# LCL_Atari_Punk_V2.net
KiCad netlist of a schematic drawn in Altium Designer
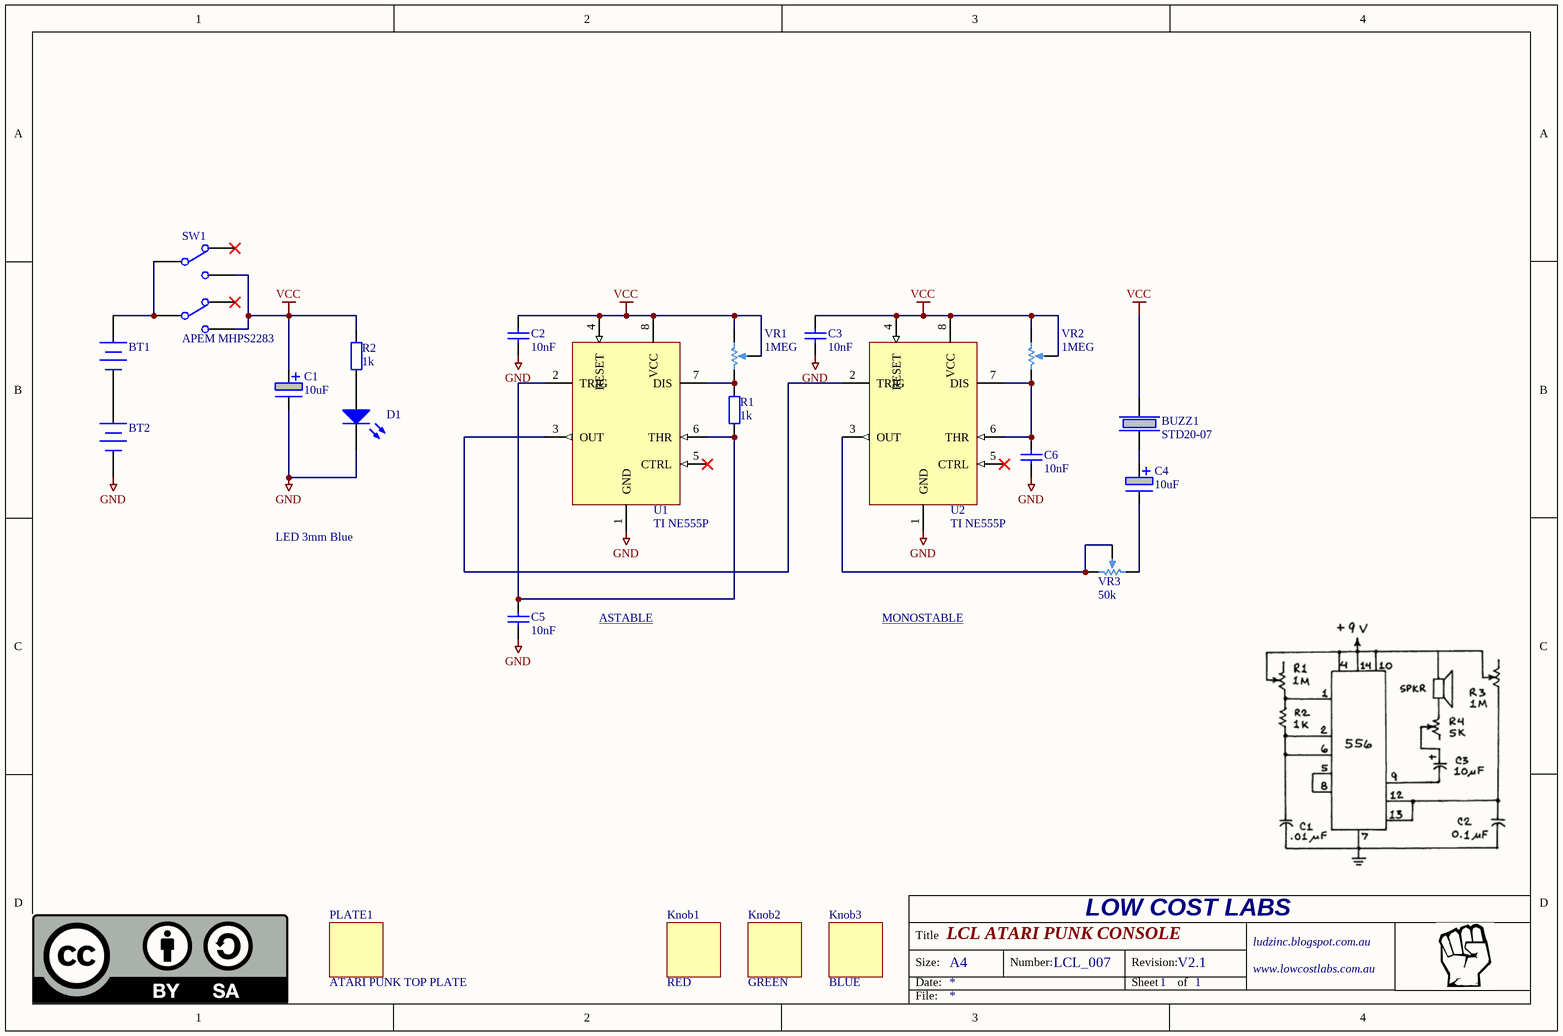
[diagram p0: LCL Atari Punk V2.SchDoc]

(export (version "E")
  (design (tool "Eeschema 10.0.6"))
  (components
    (comp (ref "BT1")
      (value "CR2032 Battery Holder")
      (footprint "PCB-dvcba8mzfnv4aqscf1uc-1")
      (description "CR2032 Battery Holder, Through Hole, Horizontal Mount")
      (libsource (lib "FavoritesLibrary") (part "SYM-19301741-1"))
    )
    (comp (ref "BT2")
      (value "CR2032 Battery Holder")
      (footprint "PCB-dvcba8mzfnv4aqscf1uc-1")
      (description "CR2032 Battery Holder, Through Hole, Horizontal Mount")
      (libsource (lib "FavoritesLibrary") (part "SYM-19301741-1"))
    )
    (comp (ref "BUZZ1")
      (value "STD20-07")
      (footprint "PCB-fy5tm47je2z5a6wt53fs-1")
      (description "BUZZER STD20-07 (EFM2060) PIEZO PASSIVE BUZZER")
      (libsource (lib "FavoritesLibrary") (part "SYM-6939a03a5900b6fe-1"))
    )
    (comp (ref "C1")
      (value "10uF")
      (footprint "PCB-ekxurobr9mz5kbw5d2ks-1")
      (description "5mm Through Hole Electrolytic 2mm Pitch, 5mm height")
      (libsource (lib "FavoritesLibrary") (part "SYM-su2zmkw1kc3z49ns9isd-1"))
    )
    (comp (ref "C2")
      (value "10nF")
      (footprint "PCB-5q3b1ntq00bqadu474q8-1")
      (description "Capacitor, Ceramic, 10000pF, 50VDC, 20-% Tol, 20+% Tol, X7R-TC Code, -15, 15%-TC")
      (fields (field (name "MANUFACTURER PART NUMBER") "C315C103M5R5TA"))
      (libsource (lib "FavoritesLibrary") (part "SYM-f9eb30fd1b76262c-1"))
    )
    (comp (ref "C3")
      (value "10nF")
      (footprint "PCB-5q3b1ntq00bqadu474q8-1")
      (description "Capacitor, Ceramic, 10000pF, 50VDC, 20-% Tol, 20+% Tol, X7R-TC Code, -15, 15%-TC")
      (fields (field (name "MANUFACTURER PART NUMBER") "C315C103M5R5TA"))
      (libsource (lib "FavoritesLibrary") (part "SYM-f9eb30fd1b76262c-1"))
    )
    (comp (ref "C4")
      (value "10uF")
      (footprint "PCB-ekxurobr9mz5kbw5d2ks-1")
      (description "5mm Through Hole Electrolytic 2mm Pitch, 5mm height")
      (libsource (lib "FavoritesLibrary") (part "SYM-su2zmkw1kc3z49ns9isd-1"))
    )
    (comp (ref "C5")
      (value "10nF")
      (footprint "PCB-5q3b1ntq00bqadu474q8-1")
      (description "Capacitor, Ceramic, 10000pF, 50VDC, 20-% Tol, 20+% Tol, X7R-TC Code, -15, 15%-TC")
      (fields (field (name "MANUFACTURER PART NUMBER") "C315C103M5R5TA"))
      (libsource (lib "FavoritesLibrary") (part "SYM-f9eb30fd1b76262c-1"))
    )
    (comp (ref "C6")
      (value "10nF")
      (footprint "PCB-5q3b1ntq00bqadu474q8-1")
      (description "Capacitor, Ceramic, 10000pF, 50VDC, 20-% Tol, 20+% Tol, X7R-TC Code, -15, 15%-TC")
      (fields (field (name "MANUFACTURER PART NUMBER") "C315C103M5R5TA"))
      (libsource (lib "FavoritesLibrary") (part "SYM-f9eb30fd1b76262c-1"))
    )
    (comp (ref "D1")
      (value "LED 3mm Blue")
      (footprint "PCB-6aozigmjsxd1tpg9bi5a-1")
      (description "3mm Blue Through Hole LED")
      (libsource (lib "FavoritesLibrary") (part "SYM-tzej1yqmv3j3170hmi0g-1"))
    )
    (comp (ref "Knob1")
      (value "RED")
      (footprint "PCB-uiy5h88ywsirsj7o87r0-1")
      (description "Pot Knob")
      (libsource (lib "FavoritesLibrary") (part "SYM-8ktywbehqx0aixue8nez-1"))
    )
    (comp (ref "Knob2")
      (value "GREEN")
      (footprint "PCB-uiy5h88ywsirsj7o87r0-1")
      (description "Pot Knob")
      (libsource (lib "FavoritesLibrary") (part "SYM-8ktywbehqx0aixue8nez-1"))
    )
    (comp (ref "Knob3")
      (value "BLUE")
      (footprint "PCB-uiy5h88ywsirsj7o87r0-1")
      (description "Pot Knob")
      (libsource (lib "FavoritesLibrary") (part "SYM-8ktywbehqx0aixue8nez-1"))
    )
    (comp (ref "PLATE1")
      (value "ATARI PUNK TOP PLATE")
      (footprint "PCB-r61ct1i2zrjc296u1a17-1")
      (description "ATARI PUNK TOP PLATE ASSEMBLY WITH 10mm STANDOFFS AND SCREWS")
      (libsource (lib "CommunityVault") (part "SYM-m1ejk5tgbv5wzvnlhkp4-1"))
    )
    (comp (ref "R1")
      (value "1k")
      (footprint "PCB-ixiz65tg090k47x3fmi7-1")
      (description "RESISITOR THROUGH HOLE 1/4W")
      (libsource (lib "FavoritesLibrary") (part "SYM-iaxfckaaxq3jb0c9euu5-1"))
    )
    (comp (ref "R2")
      (value "1k")
      (footprint "PCB-ixiz65tg090k47x3fmi7-1")
      (description "RESISITOR THROUGH HOLE 1/4W")
      (libsource (lib "FavoritesLibrary") (part "SYM-iaxfckaaxq3jb0c9euu5-1"))
    )
    (comp (ref "SW1")
      (value "APEM MHPS2283")
      (footprint "PCB-3xh7x2auc3uid3bxc76z-1")
      (description "Switch Key DPDT 0.1A 30VDC 1.76N PC Pins Thru-Hole")
      (libsource (lib "CommunityVault") (part "SYM-64d5adcf469dbb12-1"))
    )
    (comp (ref "U1")
      (value "TI NE555P")
      (footprint "DIP8-2.54-10.9X6.6MM")
      (description "Peripheral circuit; astable/monostable, timer; 10 V; 500kHz; DIP8")
      (fields (field (name "MANUFACTURER PART NUMBER") "NE555P"))
      (libsource (lib "FavoritesLibrary") (part "TI-NE555-P8"))
    )
    (comp (ref "U2")
      (value "TI NE555P")
      (footprint "DIP8-2.54-10.9X6.6MM")
      (description "Peripheral circuit; astable/monostable, timer; 10 V; 500kHz; DIP8")
      (fields (field (name "MANUFACTURER PART NUMBER") "NE555P"))
      (libsource (lib "FavoritesLibrary") (part "TI-NE555-P8"))
    )
    (comp (ref "VR1")
      (value "1MEG")
      (footprint "PCB-wc6scyizddradfuod10o-1")
      (description "P090 Series 9 mm Top Adjustment 10 kOhm ±20 % Shaft Rotary Potentiometer")
      (fields (field (name "MANUFACTURER PART NUMBER") "P090S-14T20BR10K") (field (name "Comment") "Res1"))
      (libsource (lib "CommunityVault") (part "CMP-9d2d547574b442ea-5"))
    )
    (comp (ref "VR2")
      (value "1MEG")
      (footprint "PCB-wc6scyizddradfuod10o-1")
      (description "P090 Series 9 mm Top Adjustment 10 kOhm ±20 % Shaft Rotary Potentiometer")
      (fields (field (name "MANUFACTURER PART NUMBER") "P090S-14T20BR10K") (field (name "Comment") "Res1"))
      (libsource (lib "CommunityVault") (part "CMP-9d2d547574b442ea-5"))
    )
    (comp (ref "VR3")
      (value "50k")
      (footprint "PCB-wc6scyizddradfuod10o-1")
      (description "P090 Series 9 mm Top Adjustment 10 kOhm ±20 % Shaft Rotary Potentiometer")
      (fields (field (name "MANUFACTURER PART NUMBER") "P090S-14T20BR10K") (field (name "Comment") "Res1"))
      (libsource (lib "CommunityVault") (part "CMP-9d2d547574b442ea-5"))
    )
  )
  (nets
    (net (code "1") (name "GND") (class "Default")
      (node (ref "BT2") (pin "2") (pinfunction "-_2") (pintype "passive"))
      (node (ref "C1") (pin "2") (pinfunction "2_2") (pintype "passive"))
      (node (ref "C2") (pin "1") (pinfunction "1_1") (pintype "passive"))
      (node (ref "C3") (pin "1") (pinfunction "1_1") (pintype "passive"))
      (node (ref "C5") (pin "1") (pinfunction "1_1") (pintype "passive"))
      (node (ref "C6") (pin "1") (pinfunction "1_1") (pintype "passive"))
      (node (ref "D1") (pin "2") (pinfunction "K_2") (pintype "passive"))
      (node (ref "U1") (pin "1") (pinfunction "GND_1") (pintype "power_in"))
      (node (ref "U2") (pin "1") (pinfunction "GND_1") (pintype "power_in"))
    )
    (net (code "2") (name "Net-(BT1-+)") (class "Default")
      (node (ref "BT1") (pin "1") (pinfunction "+_1") (pintype "passive"))
      (node (ref "SW1") (pin "1") (pinfunction "NO1_1") (pintype "passive"))
      (node (ref "SW1") (pin "6") (pinfunction "NO2_6") (pintype "passive"))
    )
    (net (code "3") (name "Net-(BT1--)") (class "Default")
      (node (ref "BT1") (pin "2") (pinfunction "-_2") (pintype "passive"))
      (node (ref "BT2") (pin "1") (pinfunction "+_1") (pintype "passive"))
    )
    (net (code "4") (name "Net-(BUZZ1-Pad2)") (class "Default")
      (node (ref "BUZZ1") (pin "2") (pinfunction "2_2") (pintype "passive"))
      (node (ref "C4") (pin "1") (pinfunction "1_1") (pintype "passive"))
    )
    (net (code "5") (name "Net-(D1-A)") (class "Default")
      (node (ref "D1") (pin "1") (pinfunction "A_1") (pintype "passive"))
      (node (ref "R2") (pin "1") (pinfunction "1_1") (pintype "passive"))
    )
    (net (code "6") (name "Net-(U1-DIS)") (class "Default")
      (node (ref "R1") (pin "2") (pinfunction "2_2") (pintype "passive"))
      (node (ref "U1") (pin "7") (pinfunction "DIS_7") (pintype "open_collector"))
      (node (ref "VR1") (pin "3") (pinfunction "BOT_3") (pintype "passive"))
    )
    (net (code "7") (name "Net-(U1-OUT)") (class "Default")
      (node (ref "U1") (pin "3") (pinfunction "OUT_3") (pintype "output"))
      (node (ref "U2") (pin "2") (pinfunction "TRIG_2") (pintype "passive"))
    )
    (net (code "8") (name "Net-(U1-THR)") (class "Default")
      (node (ref "C5") (pin "2") (pinfunction "2_2") (pintype "passive"))
      (node (ref "R1") (pin "1") (pinfunction "1_1") (pintype "passive"))
      (node (ref "U1") (pin "2") (pinfunction "TRIG_2") (pintype "passive"))
      (node (ref "U1") (pin "6") (pinfunction "THR_6") (pintype "input"))
    )
    (net (code "9") (name "Net-(U2-DIS)") (class "Default")
      (node (ref "C6") (pin "2") (pinfunction "2_2") (pintype "passive"))
      (node (ref "U2") (pin "6") (pinfunction "THR_6") (pintype "input"))
      (node (ref "U2") (pin "7") (pinfunction "DIS_7") (pintype "open_collector"))
      (node (ref "VR2") (pin "3") (pinfunction "BOT_3") (pintype "passive"))
    )
    (net (code "10") (name "Net-(U2-OUT)") (class "Default")
      (node (ref "U2") (pin "3") (pinfunction "OUT_3") (pintype "output"))
      (node (ref "VR3") (pin "1") (pinfunction "TOP_1") (pintype "passive"))
      (node (ref "VR3") (pin "2") (pinfunction "TAP_2") (pintype "passive"))
    )
    (net (code "11") (name "Net-(VR3-BOT)") (class "Default")
      (node (ref "C4") (pin "2") (pinfunction "2_2") (pintype "passive"))
      (node (ref "VR3") (pin "3") (pinfunction "BOT_3") (pintype "passive"))
    )
    (net (code "12") (name "VCC") (class "Default")
      (node (ref "BUZZ1") (pin "1") (pinfunction "1_1") (pintype "passive"))
      (node (ref "C1") (pin "1") (pinfunction "1_1") (pintype "passive"))
      (node (ref "C2") (pin "2") (pinfunction "2_2") (pintype "passive"))
      (node (ref "C3") (pin "2") (pinfunction "2_2") (pintype "passive"))
      (node (ref "R2") (pin "2") (pinfunction "2_2") (pintype "passive"))
      (node (ref "SW1") (pin "2") (pinfunction "NC1_2") (pintype "passive"))
      (node (ref "SW1") (pin "5") (pinfunction "NC2_5") (pintype "passive"))
      (node (ref "U1") (pin "4") (pinfunction "RESET_4") (pintype "input"))
      (node (ref "U1") (pin "8") (pinfunction "VCC_8") (pintype "power_in"))
      (node (ref "U2") (pin "4") (pinfunction "RESET_4") (pintype "input"))
      (node (ref "U2") (pin "8") (pinfunction "VCC_8") (pintype "power_in"))
      (node (ref "VR1") (pin "1") (pinfunction "TOP_1") (pintype "passive"))
      (node (ref "VR1") (pin "2") (pinfunction "TAP_2") (pintype "passive"))
      (node (ref "VR2") (pin "1") (pinfunction "TOP_1") (pintype "passive"))
      (node (ref "VR2") (pin "2") (pinfunction "TAP_2") (pintype "passive"))
    )
    (net (code "13") (name "unconnected-(SW1-COM1-Pad3)") (class "Default")
      (node (ref "SW1") (pin "3") (pinfunction "COM1_3") (pintype "passive+no_connect"))
    )
    (net (code "14") (name "unconnected-(SW1-COM2-Pad4)") (class "Default")
      (node (ref "SW1") (pin "4") (pinfunction "COM2_4") (pintype "passive+no_connect"))
    )
    (net (code "15") (name "unconnected-(U1-CTRL-Pad5)") (class "Default")
      (node (ref "U1") (pin "5") (pinfunction "CTRL_5") (pintype "input+no_connect"))
    )
    (net (code "16") (name "unconnected-(U2-CTRL-Pad5)") (class "Default")
      (node (ref "U2") (pin "5") (pinfunction "CTRL_5") (pintype "input+no_connect"))
    )
  )
)
